# Tri-color_LED_Breakout-v13.net
KiCad netlist of a schematic drawn in EAGLE
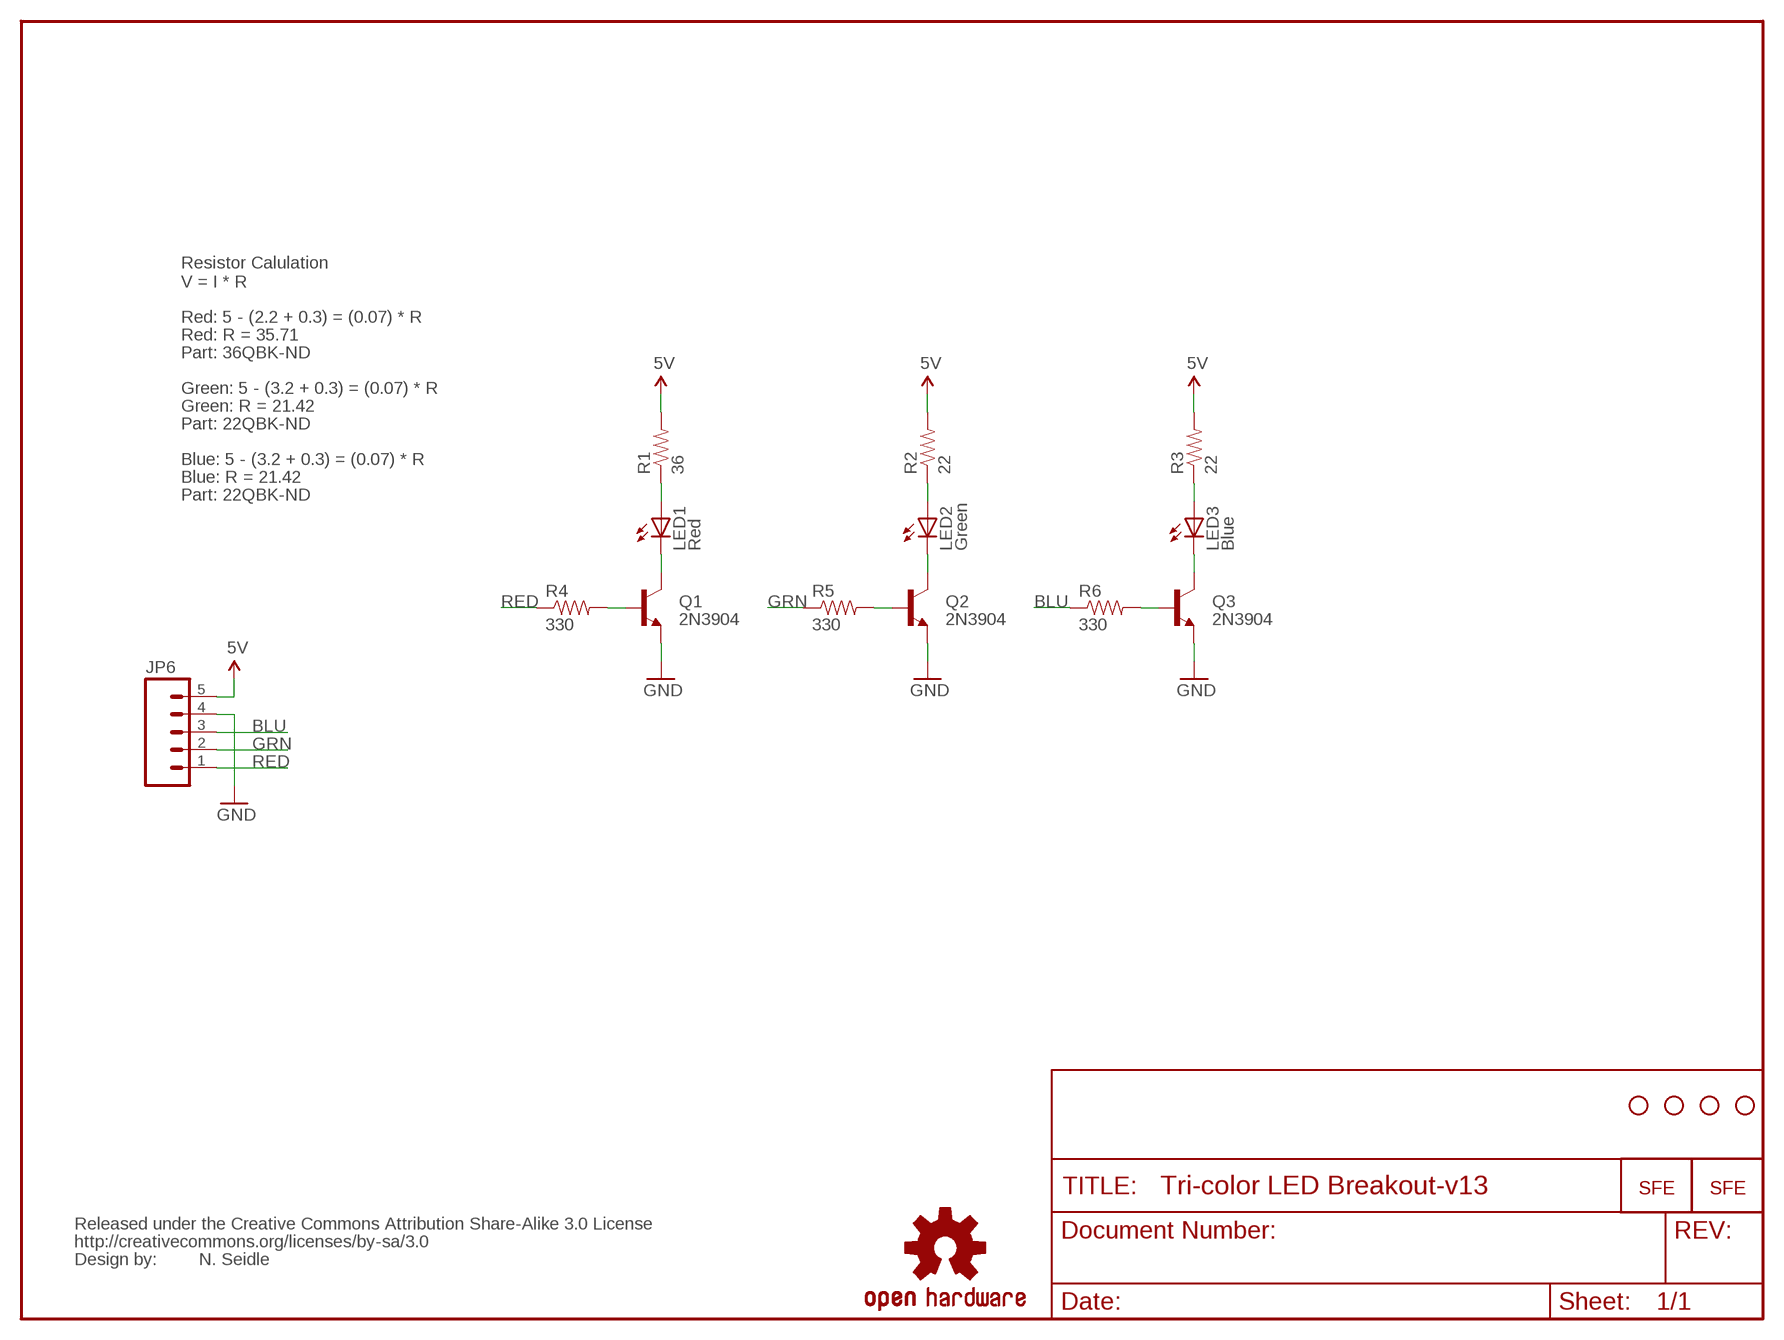
[diagram p0: schematic, sheet 1]

(export (version "E")
  (design (tool "Eeschema 10.0.6"))
  (components
    (comp (ref "JP1")
      (value "STAND-OFF")
      (footprint "eagle-import:STAND-OFF")
      (libsource (lib "eagle-import") (part "STAND-OFF"))
    )
    (comp (ref "JP2")
      (value "STAND-OFF")
      (footprint "eagle-import:STAND-OFF")
      (libsource (lib "eagle-import") (part "STAND-OFF"))
    )
    (comp (ref "JP3")
      (value "STAND-OFF")
      (footprint "eagle-import:STAND-OFF")
      (libsource (lib "eagle-import") (part "STAND-OFF"))
    )
    (comp (ref "JP4")
      (value "STAND-OFF")
      (footprint "eagle-import:STAND-OFF")
      (libsource (lib "eagle-import") (part "STAND-OFF"))
    )
    (comp (ref "JP5")
      (value "LOGO-SFESK")
      (footprint "eagle-import:SFE-LOGO-FLAME")
      (libsource (lib "eagle-import") (part "LOGO-SFESK"))
    )
    (comp (ref "JP6")
      (value "M05PTH")
      (footprint "eagle-import:1X05")
      (libsource (lib "eagle-import") (part "M05PTH"))
    )
    (comp (ref "JP7")
      (value "LOGO-SFESK")
      (footprint "eagle-import:SFE-LOGO-FLAME")
      (libsource (lib "eagle-import") (part "LOGO-SFESK"))
    )
    (comp (ref "LED1")
      (value "Red")
      (footprint "eagle-import:LED10MM")
      (libsource (lib "eagle-import") (part "LED10MM"))
    )
    (comp (ref "LED2")
      (value "Green")
      (footprint "eagle-import:LED10MM")
      (libsource (lib "eagle-import") (part "LED10MM"))
    )
    (comp (ref "LED3")
      (value "Blue")
      (footprint "eagle-import:LED10MM")
      (libsource (lib "eagle-import") (part "LED10MM"))
    )
    (comp (ref "Q1")
      (value "2N3904")
      (footprint "eagle-import:TO-92")
      (libsource (lib "eagle-import") (part "TRANSISTOR_NPNTO92"))
    )
    (comp (ref "Q2")
      (value "2N3904")
      (footprint "eagle-import:TO-92")
      (libsource (lib "eagle-import") (part "TRANSISTOR_NPNTO92"))
    )
    (comp (ref "Q3")
      (value "2N3904")
      (footprint "eagle-import:TO-92")
      (libsource (lib "eagle-import") (part "TRANSISTOR_NPNTO92"))
    )
    (comp (ref "R1")
      (value "36")
      (footprint "eagle-import:AXIAL-0.4")
      (libsource (lib "eagle-import") (part "RESISTORPTH-1/4W"))
    )
    (comp (ref "R2")
      (value "22")
      (footprint "eagle-import:AXIAL-0.4")
      (libsource (lib "eagle-import") (part "RESISTORPTH-1/4W"))
    )
    (comp (ref "R3")
      (value "22")
      (footprint "eagle-import:AXIAL-0.4")
      (libsource (lib "eagle-import") (part "RESISTORPTH-1/4W"))
    )
    (comp (ref "R4")
      (value "330")
      (footprint "eagle-import:AXIAL-0.3")
      (libsource (lib "eagle-import") (part "RESISTORAXIAL-0.3"))
    )
    (comp (ref "R5")
      (value "330")
      (footprint "eagle-import:AXIAL-0.3")
      (libsource (lib "eagle-import") (part "RESISTORAXIAL-0.3"))
    )
    (comp (ref "R6")
      (value "330")
      (footprint "eagle-import:AXIAL-0.3")
      (libsource (lib "eagle-import") (part "RESISTORAXIAL-0.3"))
    )
    (comp (ref "U$1")
      (value "CREATIVE_COMMONS")
      (footprint "eagle-import:CREATIVE_COMMONS")
      (libsource (lib "eagle-import") (part "CREATIVE_COMMONS"))
    )
    (comp (ref "U$6")
      (value "OSHW-LOGOS")
      (footprint "eagle-import:OSHW-LOGO-S")
      (libsource (lib "eagle-import") (part "OSHW-LOGOS"))
    )
  )
  (nets
    (net (code "1") (name "/BLU") (class "Default")
      (node (ref "JP6") (pin "3") (pinfunction "3_3") (pintype "passive"))
      (node (ref "R6") (pin "P$1") (pinfunction "1_P$1") (pintype "passive"))
    )
    (net (code "2") (name "/GRN") (class "Default")
      (node (ref "JP6") (pin "2") (pinfunction "2_2") (pintype "passive"))
      (node (ref "R5") (pin "P$1") (pinfunction "1_P$1") (pintype "passive"))
    )
    (net (code "3") (name "/RED") (class "Default")
      (node (ref "JP6") (pin "1") (pinfunction "1_1") (pintype "passive"))
      (node (ref "R4") (pin "P$1") (pinfunction "1_P$1") (pintype "passive"))
    )
    (net (code "4") (name "5V") (class "Default")
      (node (ref "JP6") (pin "5") (pinfunction "5_5") (pintype "passive"))
      (node (ref "R1") (pin "P$2") (pinfunction "2_P$2") (pintype "passive"))
      (node (ref "R2") (pin "P$2") (pinfunction "2_P$2") (pintype "passive"))
      (node (ref "R3") (pin "P$2") (pinfunction "2_P$2") (pintype "passive"))
    )
    (net (code "5") (name "GND") (class "Default")
      (node (ref "JP6") (pin "4") (pinfunction "4_4") (pintype "passive"))
      (node (ref "Q1") (pin "1") (pinfunction "E_1") (pintype "passive"))
      (node (ref "Q2") (pin "1") (pinfunction "E_1") (pintype "passive"))
      (node (ref "Q3") (pin "1") (pinfunction "E_1") (pintype "passive"))
    )
    (net (code "6") (name "Net-(Q1-B)") (class "Default")
      (node (ref "Q1") (pin "2") (pinfunction "B_2") (pintype "passive"))
      (node (ref "R4") (pin "P$2") (pinfunction "2_P$2") (pintype "passive"))
    )
    (net (code "7") (name "Net-(Q1-C)") (class "Default")
      (node (ref "LED1") (pin "C") (pinfunction "C_C") (pintype "passive"))
      (node (ref "Q1") (pin "3") (pinfunction "C_3") (pintype "passive"))
    )
    (net (code "8") (name "Net-(Q2-B)") (class "Default")
      (node (ref "Q2") (pin "2") (pinfunction "B_2") (pintype "passive"))
      (node (ref "R5") (pin "P$2") (pinfunction "2_P$2") (pintype "passive"))
    )
    (net (code "9") (name "Net-(Q2-C)") (class "Default")
      (node (ref "LED2") (pin "C") (pinfunction "C_C") (pintype "passive"))
      (node (ref "Q2") (pin "3") (pinfunction "C_3") (pintype "passive"))
    )
    (net (code "10") (name "Net-(Q3-B)") (class "Default")
      (node (ref "Q3") (pin "2") (pinfunction "B_2") (pintype "passive"))
      (node (ref "R6") (pin "P$2") (pinfunction "2_P$2") (pintype "passive"))
    )
    (net (code "11") (name "Net-(Q3-C)") (class "Default")
      (node (ref "LED3") (pin "C") (pinfunction "C_C") (pintype "passive"))
      (node (ref "Q3") (pin "3") (pinfunction "C_3") (pintype "passive"))
    )
    (net (code "12") (name "Net-(R1-1)") (class "Default")
      (node (ref "LED1") (pin "A") (pinfunction "A_A") (pintype "passive"))
      (node (ref "R1") (pin "P$1") (pinfunction "1_P$1") (pintype "passive"))
    )
    (net (code "13") (name "Net-(R2-1)") (class "Default")
      (node (ref "LED2") (pin "A") (pinfunction "A_A") (pintype "passive"))
      (node (ref "R2") (pin "P$1") (pinfunction "1_P$1") (pintype "passive"))
    )
    (net (code "14") (name "Net-(R3-1)") (class "Default")
      (node (ref "LED3") (pin "A") (pinfunction "A_A") (pintype "passive"))
      (node (ref "R3") (pin "P$1") (pinfunction "1_P$1") (pintype "passive"))
    )
  )
)
